# SCH_ZeeKey_2021-09-02.net
KiCad netlist of a schematic drawn in EasyEDA
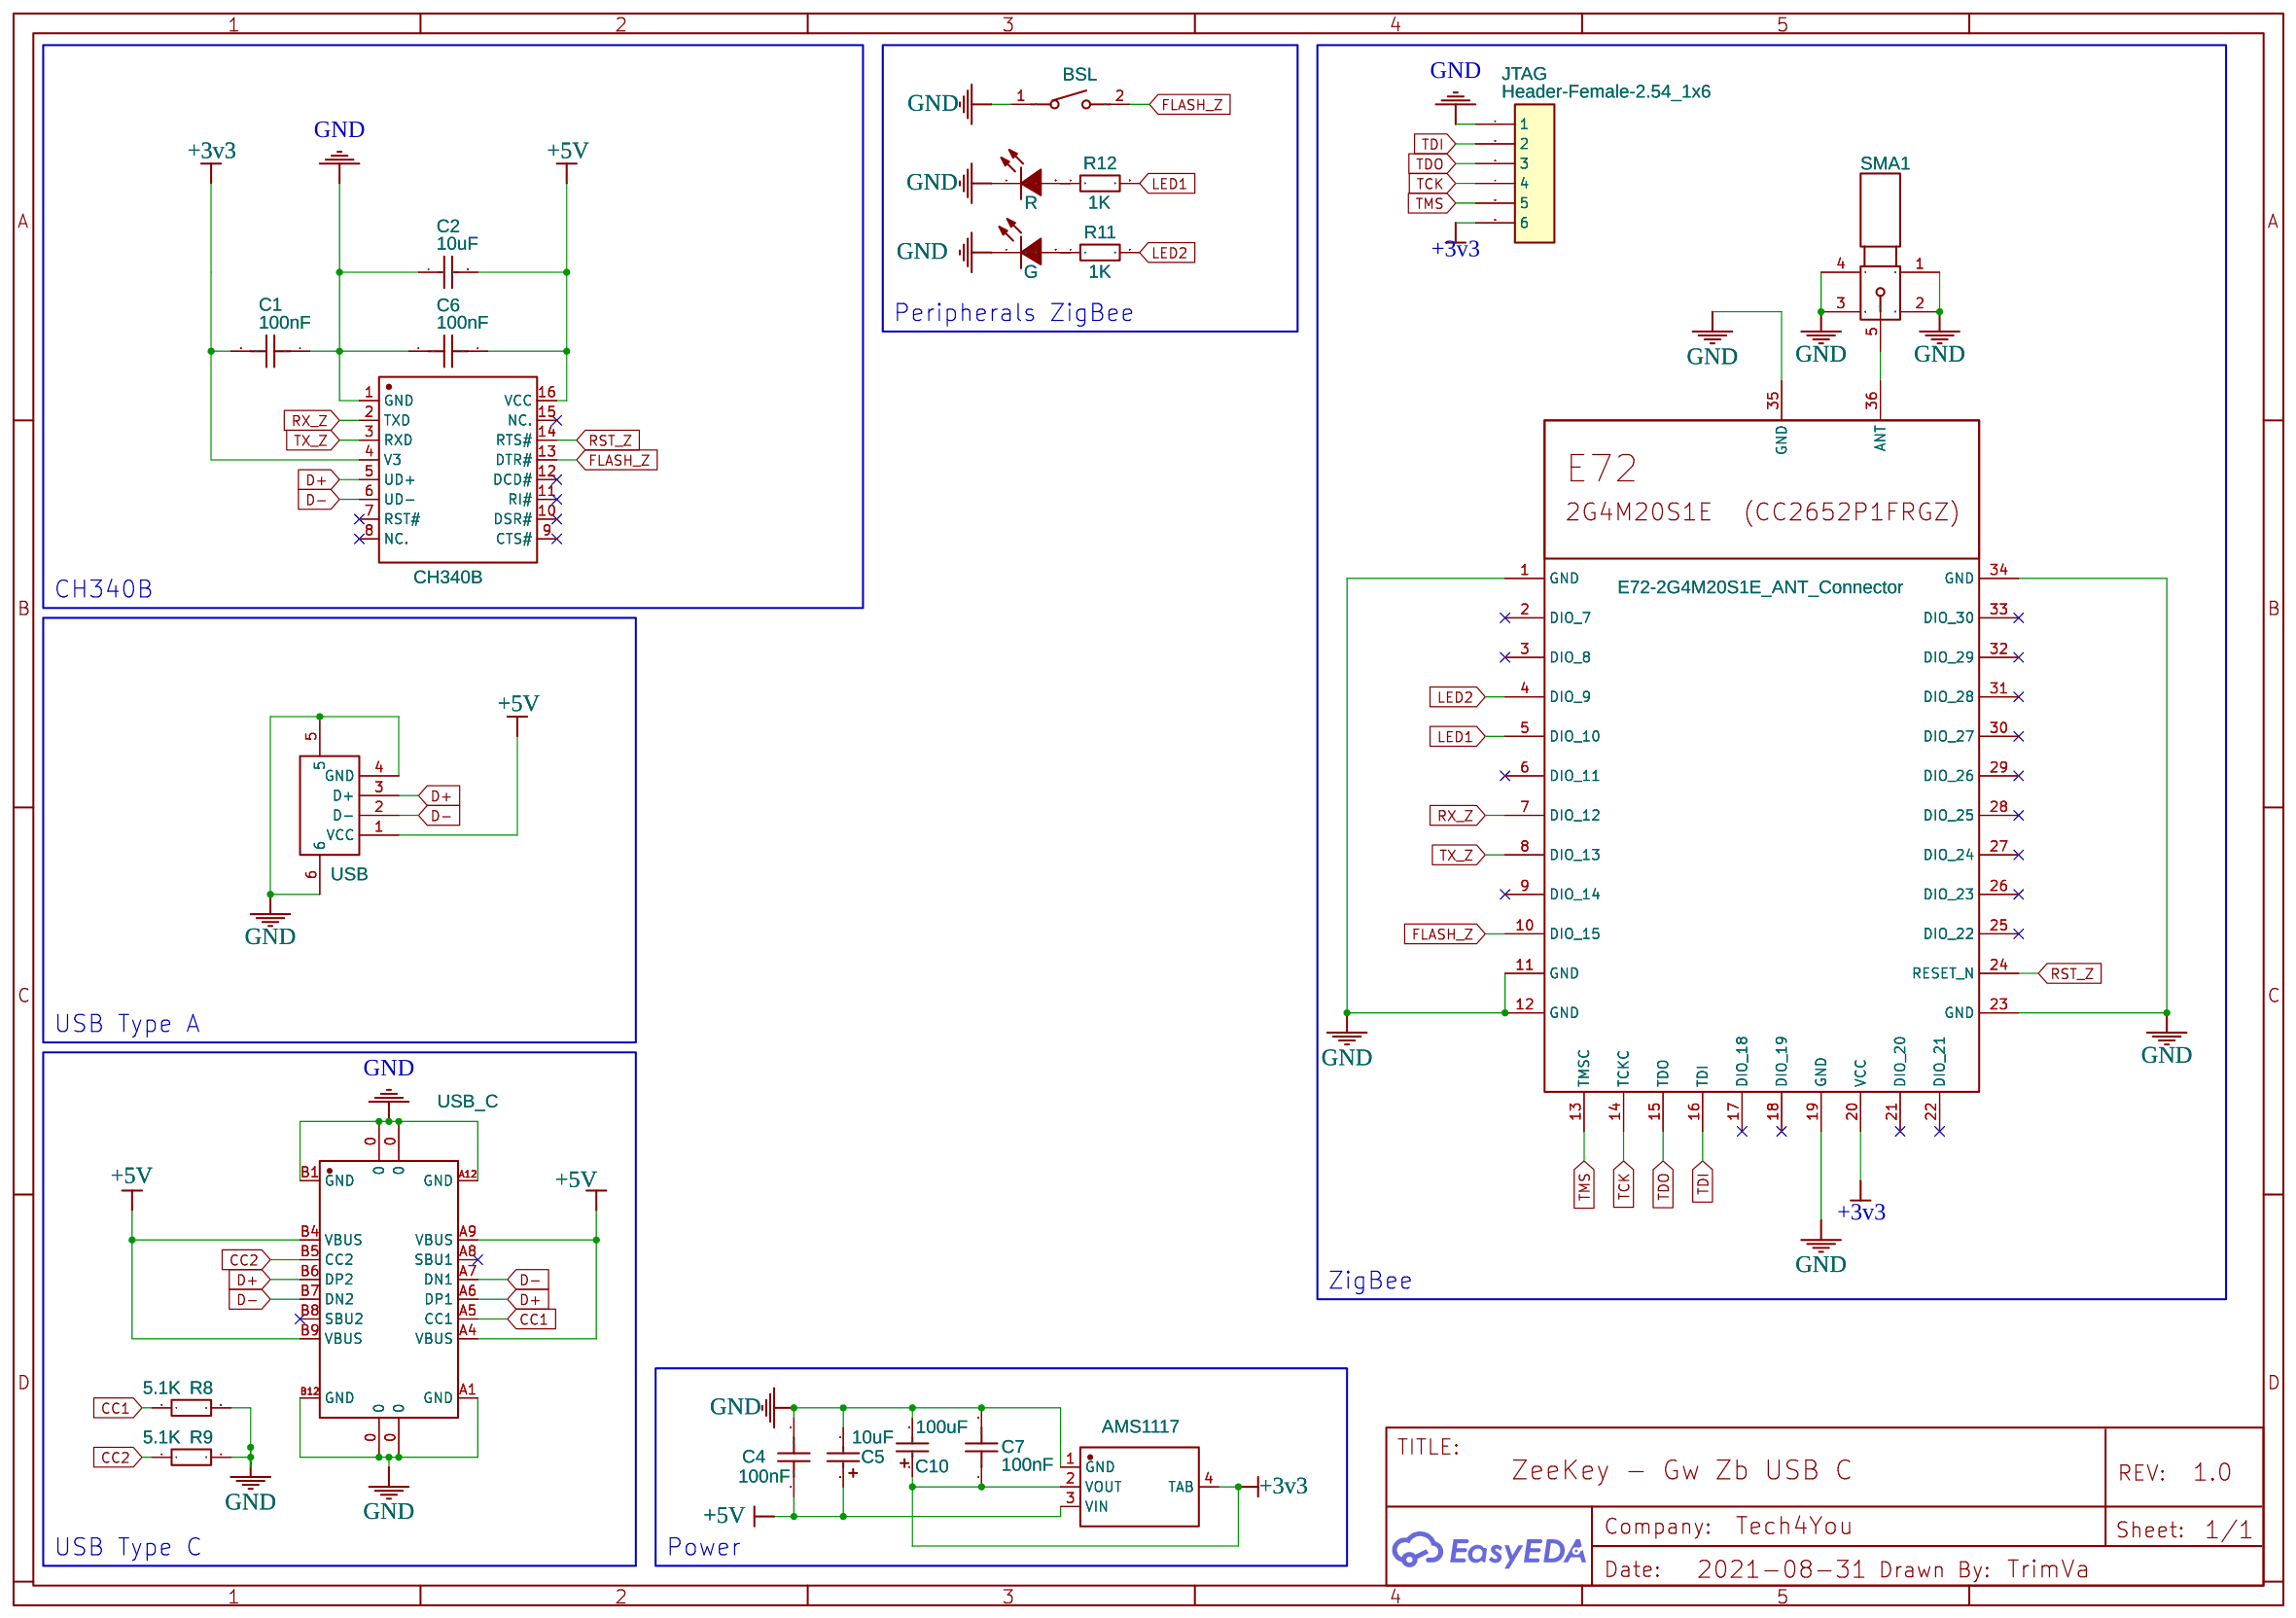
[diagram p0: schematic sheet]

(export (version "E")
  (design (tool "Eeschema 10.0.6"))
  (components
    (comp (ref "AMS1117")
      (value "AMS1117-3.3_C351784")
      (fields
        (field (name "BOM_Manufacturer Part") "AMS1117-3.3")
        (field (name "BOM_Supplier Part") "C351784")
      )
      (libsource (lib "") (part "AMS1117-3.3_C351784"))
    )
    (comp (ref "BSL")
      (value "TS-1088-AR02516")
      (fields (field (name "BOM_Supplier Part") "C720478"))
      (libsource (lib "") (part "TS-1088-AR02516"))
    )
    (comp (ref "C1")
      (value "100nF")
      (fields
        (field (name "BOM_Manufacturer Part") "C0402C104M4RACTU")
        (field (name "BOM_Supplier Part") "C170183")
      )
      (libsource (lib "") (part "C0402C104M4RACTU"))
    )
    (comp (ref "C2")
      (value "10uF")
      (fields
        (field (name "BOM_Manufacturer Part") "CL05A106MQ5NUNC")
        (field (name "BOM_Supplier Part") "C15525")
      )
      (libsource (lib "") (part "CL05A106MQ5NUNC"))
    )
    (comp (ref "C4")
      (value "100nF")
      (fields
        (field (name "BOM_Manufacturer Part") "TCC0402X7R104K160AT")
        (field (name "BOM_Supplier Part") "C392963")
      )
      (libsource (lib "") (part "TCC0402X7R104K160AT"))
    )
    (comp (ref "C5")
      (value "10uF")
      (fields
        (field (name "BOM_Manufacturer Part") "TAJA106K016RNJ")
        (field (name "BOM_Supplier Part") "C7171")
      )
      (libsource (lib "") (part "TAJA106K016RNJ"))
    )
    (comp (ref "C6")
      (value "100nF")
      (fields
        (field (name "BOM_Manufacturer Part") "C0402C104M4RACTU")
        (field (name "BOM_Supplier Part") "C170183")
      )
      (libsource (lib "") (part "C0402C104M4RACTU"))
    )
    (comp (ref "C7")
      (value "100nF")
      (fields
        (field (name "BOM_Manufacturer Part") "TCC0402X7R104K160AT")
        (field (name "BOM_Supplier Part") "C392963")
      )
      (libsource (lib "") (part "TCC0402X7R104K160AT"))
    )
    (comp (ref "C10")
      (value "100uF")
      (fields
        (field (name "BOM_Manufacturer Part") "T490A107M006ATE800")
        (field (name "BOM_Supplier Part") "C122251")
      )
      (libsource (lib "") (part "T490A107M006ATE800"))
    )
    (comp (ref "CH340B")
      (value "CH340B")
      (fields (field (name "BOM_Supplier Part") "C81010"))
      (libsource (lib "") (part "CH340B"))
    )
    (comp (ref "G")
      (value "G")
      (fields
        (field (name "BOM_Manufacturer Part") "0805G (Green)")
        (field (name "BOM_Supplier Part") "C2297")
      )
      (libsource (lib "") (part "0805G (Green)"))
    )
    (comp (ref "GND1")
      (value "E72-2G4M20S1E_ANT_Connector")
      (fields
        (field (name "BOM_Manufacturer Part") "CC2652P1FRGZ")
        (field (name "BOM_Supplier Part") "E72-2G4M20S1E")
      )
      (libsource (lib "") (part "E72-2G4M20S1E_ANT_Connector"))
    )
    (comp (ref "JTAG")
      (value "Header-Female-2.54_1x6")
      (fields (field (name "BOM_Manufacturer Part") "Female header/2.54mm2x3 Female header"))
      (libsource (lib "") (part "Header-Female-2.54_1x6"))
    )
    (comp (ref "R")
      (value "R")
      (fields
        (field (name "BOM_Manufacturer Part") "FC-2012HRK-620D")
        (field (name "BOM_Supplier Part") "C84256")
      )
      (libsource (lib "") (part "FC-2012HRK-620D"))
    )
    (comp (ref "R8")
      (value "5.1K")
      (fields
        (field (name "BOM_Manufacturer Part") "RC-02W512JT")
        (field (name "BOM_Supplier Part") "C258132")
      )
      (libsource (lib "") (part "RC-02W512JT"))
    )
    (comp (ref "R9")
      (value "5.1K")
      (fields
        (field (name "BOM_Manufacturer Part") "RC-02W512JT")
        (field (name "BOM_Supplier Part") "C258132")
      )
      (libsource (lib "") (part "RC-02W512JT"))
    )
    (comp (ref "R11")
      (value "1K")
      (fields
        (field (name "BOM_Manufacturer Part") "0402WGF1001TCE")
        (field (name "BOM_Supplier Part") "C11702")
      )
      (libsource (lib "") (part "0402WGF1001TCE"))
    )
    (comp (ref "R12")
      (value "1K")
      (fields
        (field (name "BOM_Manufacturer Part") "0402WGF1001TCE")
        (field (name "BOM_Supplier Part") "C11702")
      )
      (libsource (lib "") (part "0402WGF1001TCE"))
    )
    (comp (ref "SMA1")
      (value "BWSMA-KE-P001")
      (fields (field (name "BOM_Supplier Part") "C496550"))
      (libsource (lib "") (part "BWSMA-KE-P001"))
    )
    (comp (ref "USB")
      (value "U217-04XN-XXR84")
      (fields (field (name "BOM_Supplier Part") "C319178"))
      (libsource (lib "") (part "U217-04XN-XXR84"))
    )
    (comp (ref "USB_C")
      (value "TYPE-C-31-M-12")
      (fields (field (name "BOM_Supplier Part") "C165948"))
      (libsource (lib "") (part "TYPE-C-31-M-12"))
    )
  )
  (nets
    (net (code "1") (name "+3v3") (class "Default")
      (node (ref "AMS1117") (pin "2") (pinfunction "VOUT_2") (pintype "unspecified"))
      (node (ref "AMS1117") (pin "4") (pinfunction "TAB_4") (pintype "unspecified"))
      (node (ref "C1") (pin "2") (pinfunction "2_2") (pintype "unspecified"))
      (node (ref "C10") (pin "1") (pinfunction "1_1") (pintype "input"))
      (node (ref "C7") (pin "1") (pinfunction "1_1") (pintype "unspecified"))
      (node (ref "CH340B") (pin "4") (pinfunction "V3_4") (pintype "unspecified"))
      (node (ref "GND1") (pin "20") (pinfunction "VCC_20") (pintype "unspecified"))
      (node (ref "JTAG") (pin "6") (pinfunction "6_6") (pintype "input"))
    )
    (net (code "2") (name "+5V") (class "Default")
      (node (ref "AMS1117") (pin "3") (pinfunction "VIN_3") (pintype "unspecified"))
      (node (ref "C2") (pin "2") (pinfunction "2_2") (pintype "input"))
      (node (ref "C4") (pin "1") (pinfunction "1_1") (pintype "unspecified"))
      (node (ref "C5") (pin "1") (pinfunction "1_1") (pintype "input"))
      (node (ref "C6") (pin "1") (pinfunction "1_1") (pintype "unspecified"))
      (node (ref "CH340B") (pin "16") (pinfunction "VCC_16") (pintype "unspecified"))
      (node (ref "USB") (pin "1") (pinfunction "VCC_1") (pintype "unspecified"))
      (node (ref "USB_C") (pin "A4") (pinfunction "VBUS_A4") (pintype "unspecified"))
      (node (ref "USB_C") (pin "A9") (pinfunction "VBUS_A9") (pintype "unspecified"))
      (node (ref "USB_C") (pin "B4") (pinfunction "VBUS_B4") (pintype "unspecified"))
      (node (ref "USB_C") (pin "B9") (pinfunction "VBUS_B9") (pintype "unspecified"))
    )
    (net (code "3") (name "CC1") (class "Default")
      (node (ref "R8") (pin "1") (pinfunction "1_1") (pintype "unspecified"))
      (node (ref "USB_C") (pin "A5") (pinfunction "CC1_A5") (pintype "unspecified"))
    )
    (net (code "4") (name "CC2") (class "Default")
      (node (ref "R9") (pin "1") (pinfunction "1_1") (pintype "unspecified"))
      (node (ref "USB_C") (pin "B5") (pinfunction "CC2_B5") (pintype "unspecified"))
    )
    (net (code "5") (name "D+") (class "Default")
      (node (ref "CH340B") (pin "5") (pinfunction "UD+_5") (pintype "unspecified"))
      (node (ref "USB") (pin "3") (pinfunction "D+_3") (pintype "unspecified"))
      (node (ref "USB_C") (pin "A6") (pinfunction "DP1_A6") (pintype "unspecified"))
      (node (ref "USB_C") (pin "B6") (pinfunction "DP2_B6") (pintype "unspecified"))
    )
    (net (code "6") (name "D-") (class "Default")
      (node (ref "CH340B") (pin "6") (pinfunction "UD-_6") (pintype "unspecified"))
      (node (ref "USB") (pin "2") (pinfunction "D-_2") (pintype "unspecified"))
      (node (ref "USB_C") (pin "A7") (pinfunction "DN1_A7") (pintype "unspecified"))
      (node (ref "USB_C") (pin "B7") (pinfunction "DN2_B7") (pintype "unspecified"))
    )
    (net (code "7") (name "FLASH_Z") (class "Default")
      (node (ref "BSL") (pin "2") (pinfunction "2_2") (pintype "unspecified"))
      (node (ref "CH340B") (pin "13") (pinfunction "DTR#_13") (pintype "unspecified"))
      (node (ref "GND1") (pin "10") (pinfunction "DIO_15_10") (pintype "unspecified"))
    )
    (net (code "8") (name "GND") (class "Default")
      (node (ref "AMS1117") (pin "1") (pinfunction "GND_1") (pintype "unspecified"))
      (node (ref "BSL") (pin "1") (pinfunction "1_1") (pintype "unspecified"))
      (node (ref "C1") (pin "1") (pinfunction "1_1") (pintype "unspecified"))
      (node (ref "C10") (pin "2") (pinfunction "2_2") (pintype "input"))
      (node (ref "C2") (pin "1") (pinfunction "1_1") (pintype "input"))
      (node (ref "C4") (pin "2") (pinfunction "2_2") (pintype "unspecified"))
      (node (ref "C5") (pin "2") (pinfunction "2_2") (pintype "input"))
      (node (ref "C6") (pin "2") (pinfunction "2_2") (pintype "unspecified"))
      (node (ref "C7") (pin "2") (pinfunction "2_2") (pintype "unspecified"))
      (node (ref "CH340B") (pin "1") (pinfunction "GND_1") (pintype "unspecified"))
      (node (ref "G") (pin "1") (pinfunction "K_1") (pintype "unspecified"))
      (node (ref "GND1") (pin "1") (pinfunction "GND_1") (pintype "unspecified"))
      (node (ref "GND1") (pin "11") (pinfunction "GND_11") (pintype "unspecified"))
      (node (ref "GND1") (pin "12") (pinfunction "GND_12") (pintype "unspecified"))
      (node (ref "GND1") (pin "19") (pinfunction "GND_19") (pintype "unspecified"))
      (node (ref "GND1") (pin "23") (pinfunction "GND_23") (pintype "unspecified"))
      (node (ref "GND1") (pin "34") (pinfunction "GND_34") (pintype "unspecified"))
      (node (ref "GND1") (pin "35") (pinfunction "GND_35") (pintype "unspecified"))
      (node (ref "JTAG") (pin "1") (pinfunction "1_1") (pintype "input"))
      (node (ref "R") (pin "1") (pinfunction "-_1") (pintype "unspecified"))
      (node (ref "R8") (pin "2") (pinfunction "2_2") (pintype "unspecified"))
      (node (ref "R9") (pin "2") (pinfunction "2_2") (pintype "unspecified"))
      (node (ref "SMA1") (pin "1") (pinfunction "1_1") (pintype "unspecified"))
      (node (ref "SMA1") (pin "2") (pinfunction "2_2") (pintype "unspecified"))
      (node (ref "SMA1") (pin "3") (pinfunction "3_3") (pintype "unspecified"))
      (node (ref "SMA1") (pin "4") (pinfunction "4_4") (pintype "unspecified"))
      (node (ref "USB") (pin "4") (pinfunction "GND_4") (pintype "unspecified"))
      (node (ref "USB") (pin "5") (pinfunction "5_5") (pintype "unspecified"))
      (node (ref "USB") (pin "6") (pinfunction "6_6") (pintype "unspecified"))
      (node (ref "USB_C") (pin "0") (pinfunction "0_0") (pintype "unspecified"))
      (node (ref "USB_C") (pin "A1") (pinfunction "GND_A1") (pintype "unspecified"))
      (node (ref "USB_C") (pin "A12") (pinfunction "GND_A12") (pintype "unspecified"))
      (node (ref "USB_C") (pin "B1") (pinfunction "GND_B1") (pintype "unspecified"))
      (node (ref "USB_C") (pin "B12") (pinfunction "GND_B12") (pintype "unspecified"))
    )
    (net (code "9") (name "LED1") (class "Default")
      (node (ref "GND1") (pin "5") (pinfunction "DIO_10_5") (pintype "unspecified"))
      (node (ref "R12") (pin "2") (pinfunction "2_2") (pintype "input"))
    )
    (net (code "10") (name "LED2") (class "Default")
      (node (ref "GND1") (pin "4") (pinfunction "DIO_9_4") (pintype "unspecified"))
      (node (ref "R11") (pin "2") (pinfunction "2_2") (pintype "input"))
    )
    (net (code "11") (name "Net-(G-A)") (class "Default")
      (node (ref "G") (pin "2") (pinfunction "A_2") (pintype "unspecified"))
      (node (ref "R11") (pin "1") (pinfunction "1_1") (pintype "input"))
    )
    (net (code "12") (name "Net-(GND1-ANT)") (class "Default")
      (node (ref "GND1") (pin "36") (pinfunction "ANT_36") (pintype "unspecified"))
      (node (ref "SMA1") (pin "5") (pinfunction "5_5") (pintype "unspecified"))
    )
    (net (code "13") (name "Net-(R-+)") (class "Default")
      (node (ref "R") (pin "2") (pinfunction "+_2") (pintype "unspecified"))
      (node (ref "R12") (pin "1") (pinfunction "1_1") (pintype "input"))
    )
    (net (code "14") (name "RST_Z") (class "Default")
      (node (ref "CH340B") (pin "14") (pinfunction "RTS#_14") (pintype "unspecified"))
      (node (ref "GND1") (pin "24") (pinfunction "RESET_N_24") (pintype "unspecified"))
    )
    (net (code "15") (name "RX_Z") (class "Default")
      (node (ref "CH340B") (pin "2") (pinfunction "TXD_2") (pintype "unspecified"))
      (node (ref "GND1") (pin "7") (pinfunction "DIO_12_7") (pintype "unspecified"))
    )
    (net (code "16") (name "TCK") (class "Default")
      (node (ref "GND1") (pin "14") (pinfunction "TCKC_14") (pintype "unspecified"))
      (node (ref "JTAG") (pin "4") (pinfunction "4_4") (pintype "input"))
    )
    (net (code "17") (name "TDI") (class "Default")
      (node (ref "GND1") (pin "16") (pinfunction "TDI_16") (pintype "unspecified"))
      (node (ref "JTAG") (pin "2") (pinfunction "2_2") (pintype "input"))
    )
    (net (code "18") (name "TDO") (class "Default")
      (node (ref "GND1") (pin "15") (pinfunction "TDO_15") (pintype "unspecified"))
      (node (ref "JTAG") (pin "3") (pinfunction "3_3") (pintype "input"))
    )
    (net (code "19") (name "TMS") (class "Default")
      (node (ref "GND1") (pin "13") (pinfunction "TMSC_13") (pintype "unspecified"))
      (node (ref "JTAG") (pin "5") (pinfunction "5_5") (pintype "input"))
    )
    (net (code "20") (name "TX_Z") (class "Default")
      (node (ref "CH340B") (pin "3") (pinfunction "RXD_3") (pintype "unspecified"))
      (node (ref "GND1") (pin "8") (pinfunction "DIO_13_8") (pintype "unspecified"))
    )
    (net (code "21") (name "unconnected-(CH340B-CTS#-Pad9)") (class "Default")
      (node (ref "CH340B") (pin "9") (pinfunction "CTS#_9") (pintype "unspecified+no_connect"))
    )
    (net (code "22") (name "unconnected-(CH340B-DCD#-Pad12)") (class "Default")
      (node (ref "CH340B") (pin "12") (pinfunction "DCD#_12") (pintype "unspecified+no_connect"))
    )
    (net (code "23") (name "unconnected-(CH340B-DSR#-Pad10)") (class "Default")
      (node (ref "CH340B") (pin "10") (pinfunction "DSR#_10") (pintype "unspecified+no_connect"))
    )
    (net (code "24") (name "unconnected-(CH340B-NC.-Pad8)") (class "Default")
      (node (ref "CH340B") (pin "8") (pinfunction "NC._8") (pintype "unspecified+no_connect"))
    )
    (net (code "25") (name "unconnected-(CH340B-NC.-Pad15)") (class "Default")
      (node (ref "CH340B") (pin "15") (pinfunction "NC._15") (pintype "unspecified+no_connect"))
    )
    (net (code "26") (name "unconnected-(CH340B-RI#-Pad11)") (class "Default")
      (node (ref "CH340B") (pin "11") (pinfunction "RI#_11") (pintype "unspecified+no_connect"))
    )
    (net (code "27") (name "unconnected-(CH340B-RST#-Pad7)") (class "Default")
      (node (ref "CH340B") (pin "7") (pinfunction "RST#_7") (pintype "unspecified+no_connect"))
    )
    (net (code "28") (name "unconnected-(GND1-DIO_7-Pad2)") (class "Default")
      (node (ref "GND1") (pin "2") (pinfunction "DIO_7_2") (pintype "unspecified+no_connect"))
    )
    (net (code "29") (name "unconnected-(GND1-DIO_8-Pad3)") (class "Default")
      (node (ref "GND1") (pin "3") (pinfunction "DIO_8_3") (pintype "unspecified+no_connect"))
    )
    (net (code "30") (name "unconnected-(GND1-DIO_11-Pad6)") (class "Default")
      (node (ref "GND1") (pin "6") (pinfunction "DIO_11_6") (pintype "unspecified+no_connect"))
    )
    (net (code "31") (name "unconnected-(GND1-DIO_14-Pad9)") (class "Default")
      (node (ref "GND1") (pin "9") (pinfunction "DIO_14_9") (pintype "unspecified+no_connect"))
    )
    (net (code "32") (name "unconnected-(GND1-DIO_18-Pad17)") (class "Default")
      (node (ref "GND1") (pin "17") (pinfunction "DIO_18_17") (pintype "unspecified+no_connect"))
    )
    (net (code "33") (name "unconnected-(GND1-DIO_19-Pad18)") (class "Default")
      (node (ref "GND1") (pin "18") (pinfunction "DIO_19_18") (pintype "unspecified+no_connect"))
    )
    (net (code "34") (name "unconnected-(GND1-DIO_20-Pad21)") (class "Default")
      (node (ref "GND1") (pin "21") (pinfunction "DIO_20_21") (pintype "unspecified+no_connect"))
    )
    (net (code "35") (name "unconnected-(GND1-DIO_21-Pad22)") (class "Default")
      (node (ref "GND1") (pin "22") (pinfunction "DIO_21_22") (pintype "unspecified+no_connect"))
    )
    (net (code "36") (name "unconnected-(GND1-DIO_22-Pad25)") (class "Default")
      (node (ref "GND1") (pin "25") (pinfunction "DIO_22_25") (pintype "unspecified+no_connect"))
    )
    (net (code "37") (name "unconnected-(GND1-DIO_23-Pad26)") (class "Default")
      (node (ref "GND1") (pin "26") (pinfunction "DIO_23_26") (pintype "unspecified+no_connect"))
    )
    (net (code "38") (name "unconnected-(GND1-DIO_24-Pad27)") (class "Default")
      (node (ref "GND1") (pin "27") (pinfunction "DIO_24_27") (pintype "unspecified+no_connect"))
    )
    (net (code "39") (name "unconnected-(GND1-DIO_25-Pad28)") (class "Default")
      (node (ref "GND1") (pin "28") (pinfunction "DIO_25_28") (pintype "unspecified+no_connect"))
    )
    (net (code "40") (name "unconnected-(GND1-DIO_26-Pad29)") (class "Default")
      (node (ref "GND1") (pin "29") (pinfunction "DIO_26_29") (pintype "unspecified+no_connect"))
    )
    (net (code "41") (name "unconnected-(GND1-DIO_27-Pad30)") (class "Default")
      (node (ref "GND1") (pin "30") (pinfunction "DIO_27_30") (pintype "unspecified+no_connect"))
    )
    (net (code "42") (name "unconnected-(GND1-DIO_28-Pad31)") (class "Default")
      (node (ref "GND1") (pin "31") (pinfunction "DIO_28_31") (pintype "unspecified+no_connect"))
    )
    (net (code "43") (name "unconnected-(GND1-DIO_29-Pad32)") (class "Default")
      (node (ref "GND1") (pin "32") (pinfunction "DIO_29_32") (pintype "unspecified+no_connect"))
    )
    (net (code "44") (name "unconnected-(GND1-DIO_30-Pad33)") (class "Default")
      (node (ref "GND1") (pin "33") (pinfunction "DIO_30_33") (pintype "unspecified+no_connect"))
    )
    (net (code "45") (name "unconnected-(USB_C-SBU1-PadA8)") (class "Default")
      (node (ref "USB_C") (pin "A8") (pinfunction "SBU1_A8") (pintype "unspecified+no_connect"))
    )
    (net (code "46") (name "unconnected-(USB_C-SBU2-PadB8)") (class "Default")
      (node (ref "USB_C") (pin "B8") (pinfunction "SBU2_B8") (pintype "unspecified+no_connect"))
    )
  )
)
